# GS_01_Core.net
KiCad netlist of a schematic drawn in Altium Designer
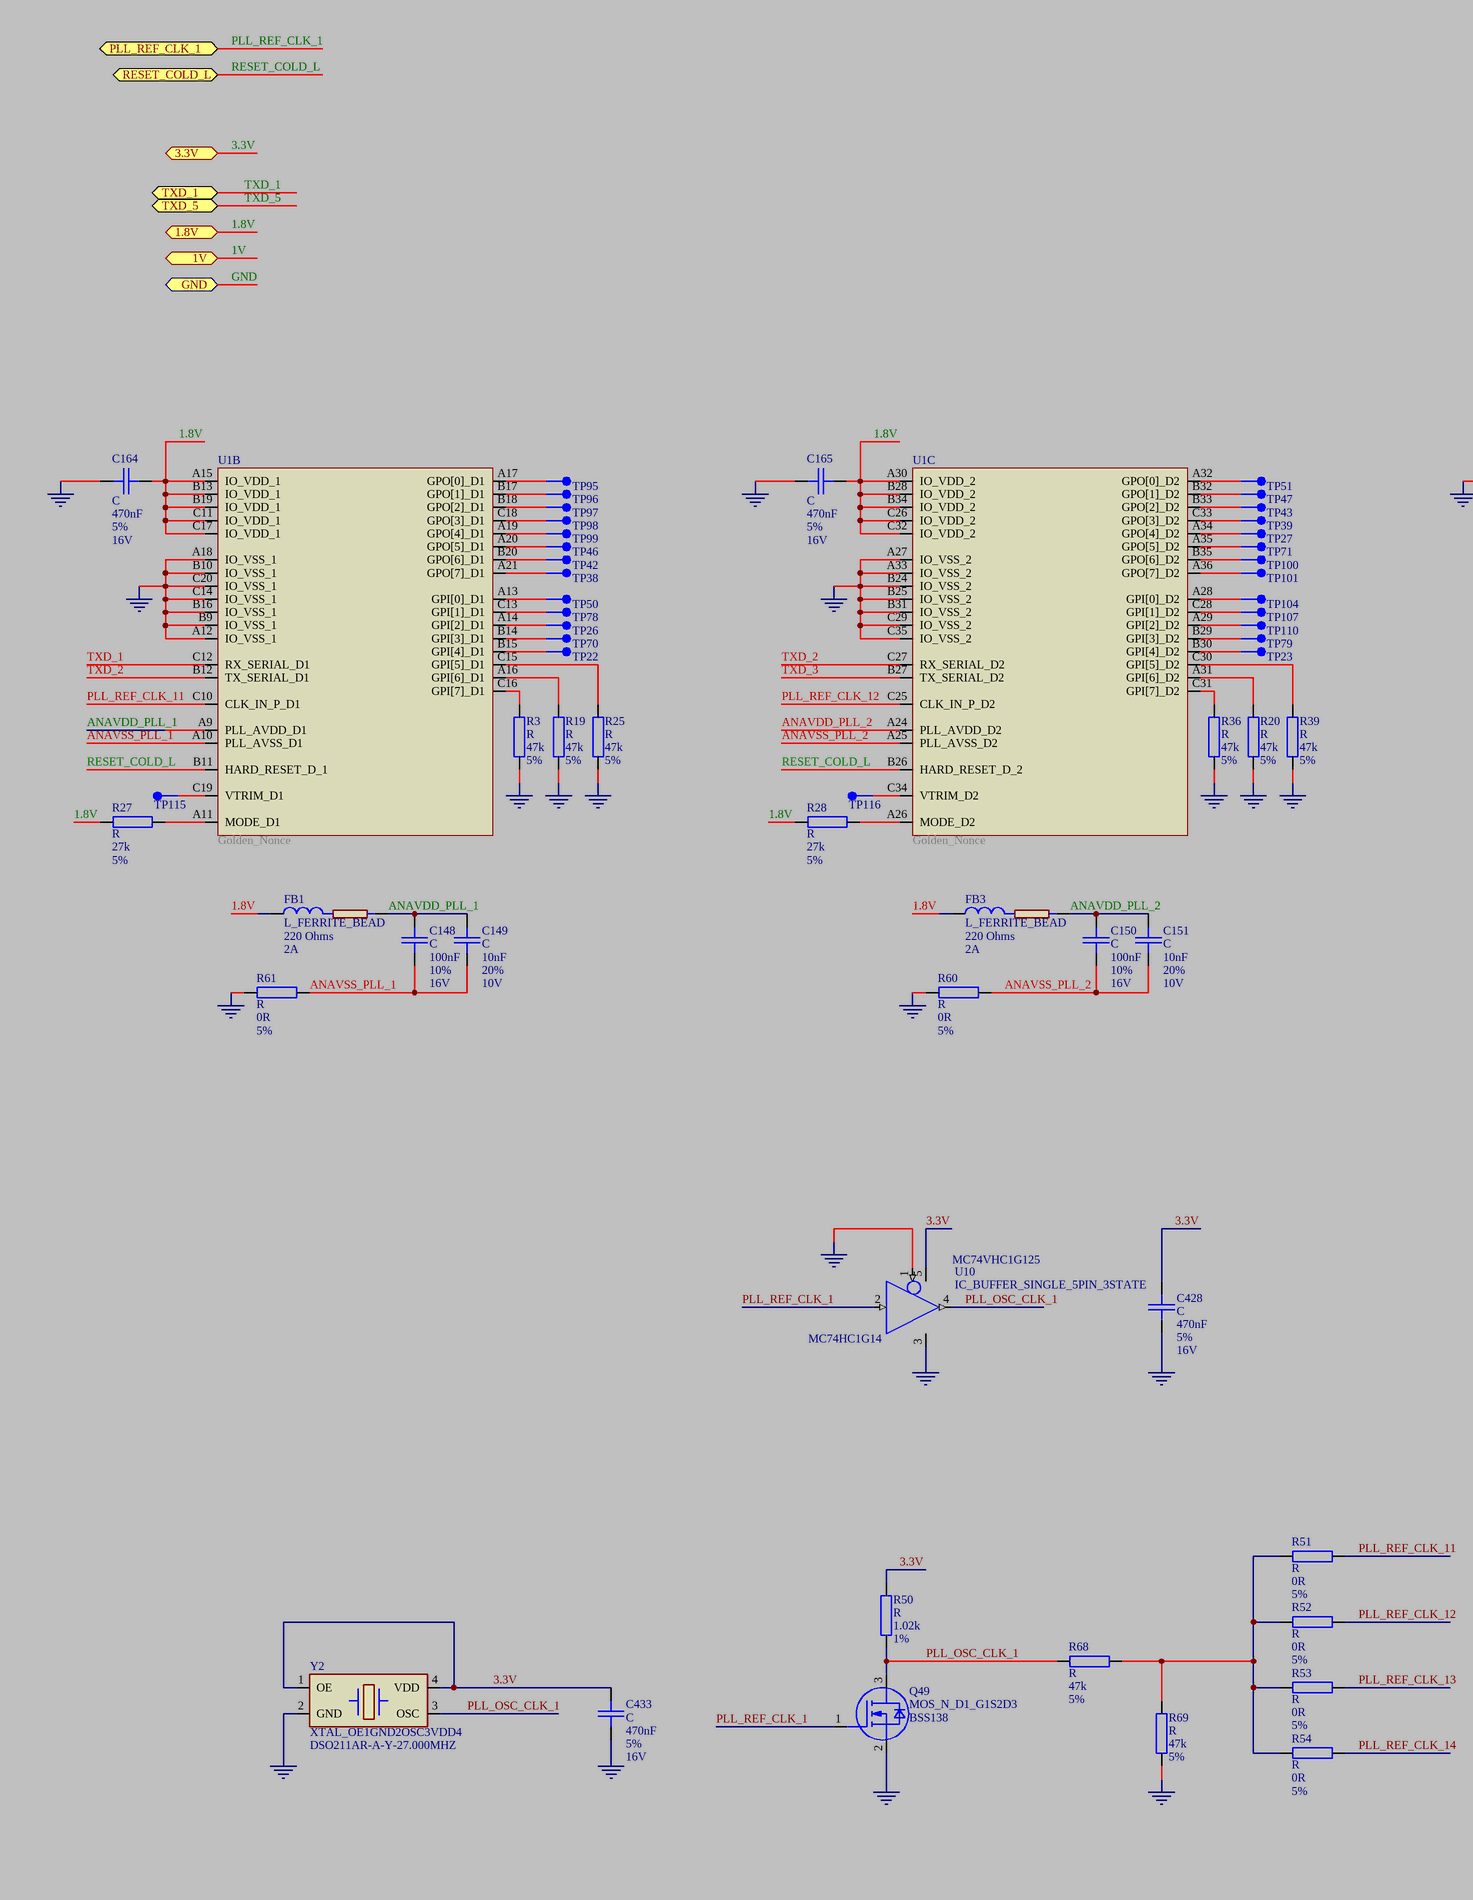
[diagram p0: GS_01_Core.SchDoc, left]
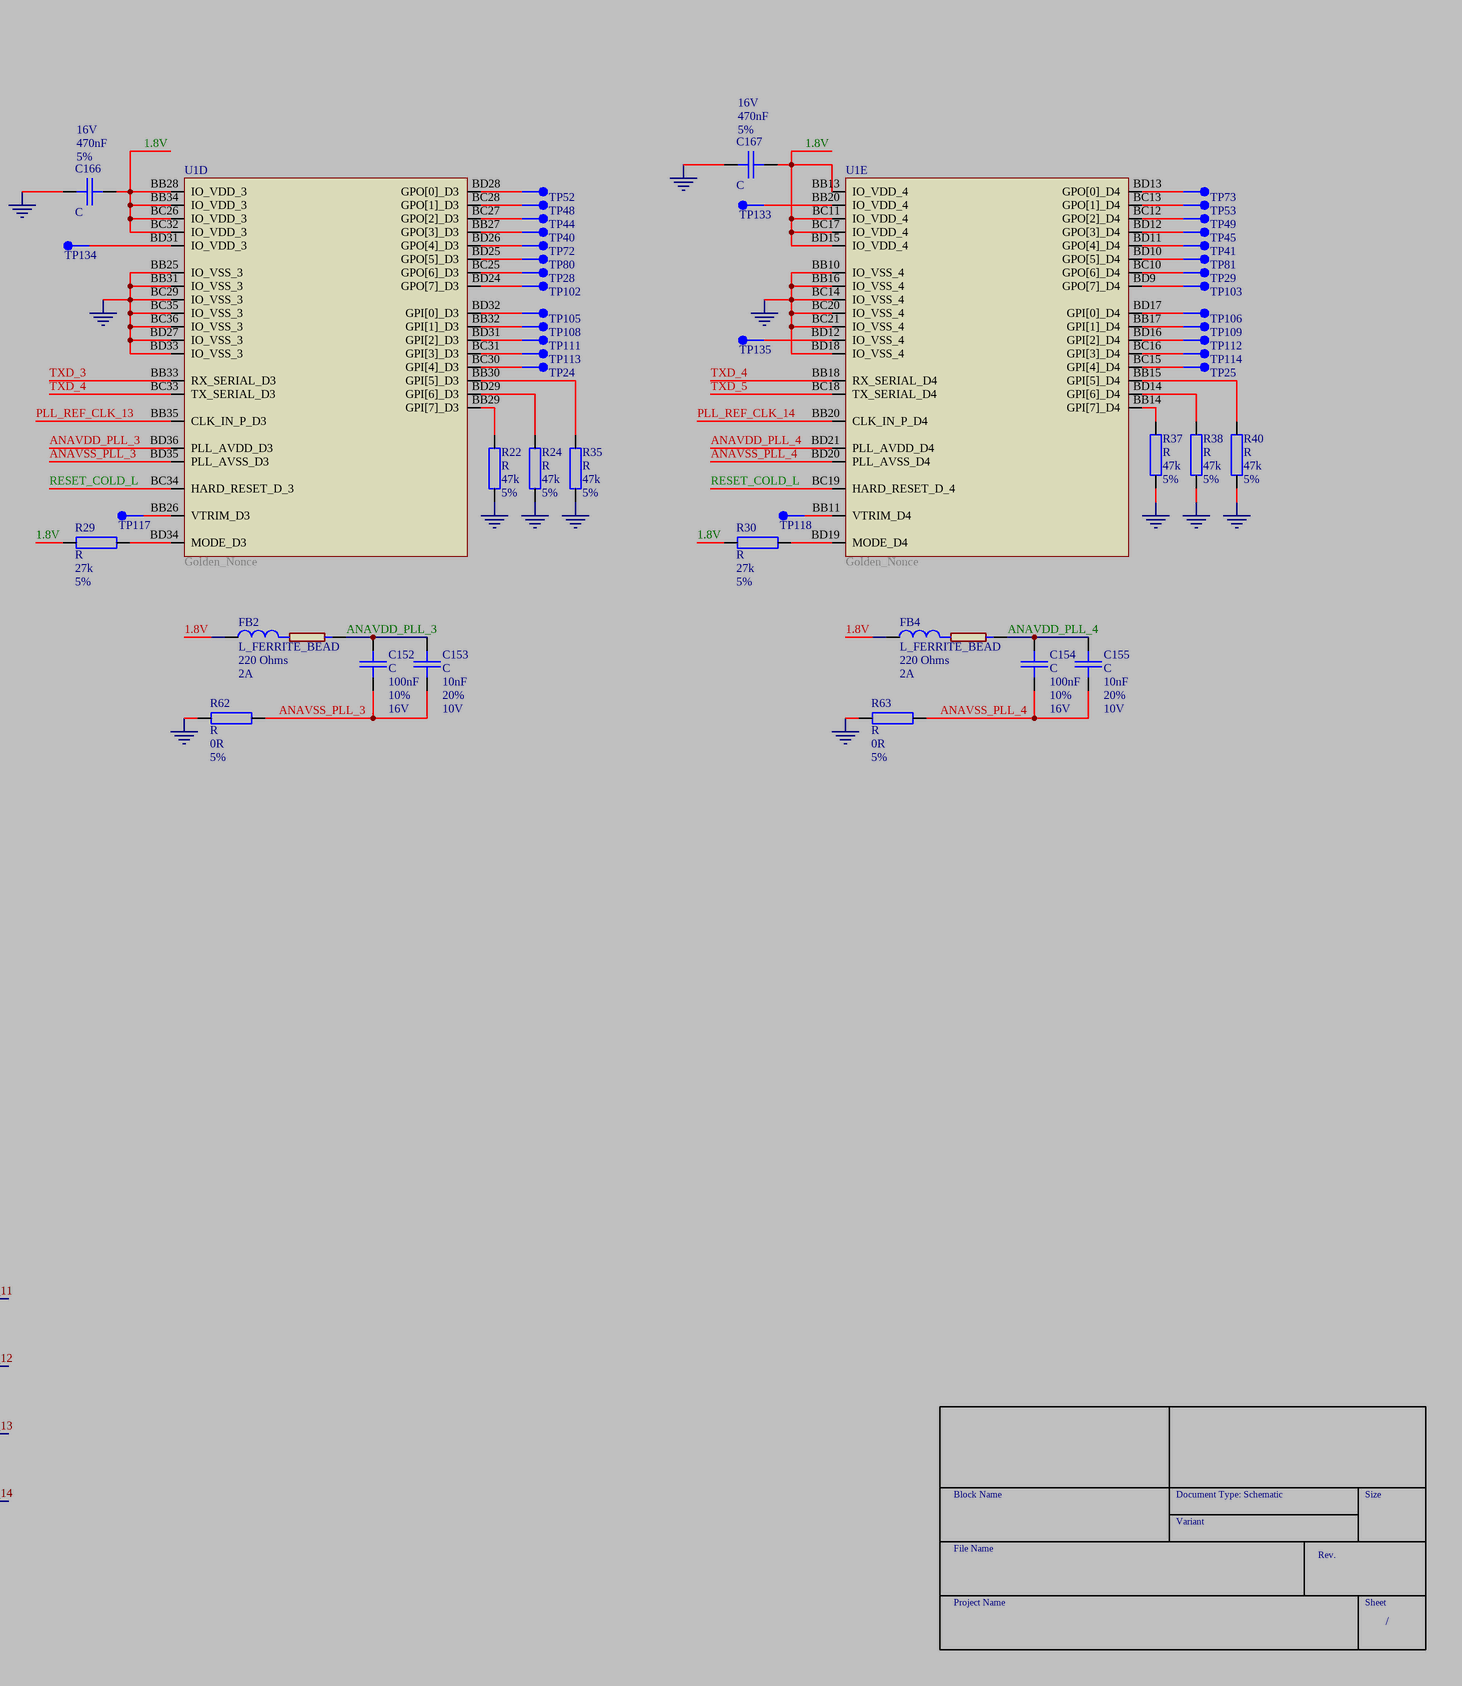
[diagram p1: GS_01_Core.SchDoc, right]

(export (version "E")
  (design (tool "Eeschema 10.0.6"))
  (components
    (comp (ref "C148")
      (value "C")
      (footprint "SMD_0603_CAPC1608X95N")
      (fields
        (field (name "DB_PART_NUMBER") "CAP000047357")
        (field (name "DB_VALUE") "100nF")
        (field (name "DB_TOLERANCE") "10%")
        (field (name "DB_VOLTAGE") "16V")
        (field (name "DB_MANUFACTURER_PART") "YAGEO      223878615649")
        (field (name "DB_APPROVED_BY") "VSN")
      )
      (libsource (lib "Database_Libs1") (part "C"))
    )
    (comp (ref "C149")
      (value "C")
      (footprint "SMD_0603_CAPC1608X95N")
      (fields
        (field (name "DB_PART_NUMBER") "CAP000038821")
        (field (name "DB_VALUE") "10nF")
        (field (name "DB_TOLERANCE") "20%")
        (field (name "DB_VOLTAGE") "10V")
        (field (name "DB_MANUFACTURER_PART") "KEMET    C0603C103M8GAC")
      )
      (libsource (lib "Database_Libs1") (part "C"))
    )
    (comp (ref "C150")
      (value "C")
      (footprint "SMD_0603_CAPC1608X95N")
      (fields
        (field (name "DB_PART_NUMBER") "CAP000047357")
        (field (name "DB_VALUE") "100nF")
        (field (name "DB_TOLERANCE") "10%")
        (field (name "DB_VOLTAGE") "16V")
        (field (name "DB_MANUFACTURER_PART") "YAGEO      223878615649")
        (field (name "DB_APPROVED_BY") "VSN")
      )
      (libsource (lib "Database_Libs1") (part "C"))
    )
    (comp (ref "C151")
      (value "C")
      (footprint "SMD_0603_CAPC1608X95N")
      (fields
        (field (name "DB_PART_NUMBER") "CAP000038821")
        (field (name "DB_VALUE") "10nF")
        (field (name "DB_TOLERANCE") "20%")
        (field (name "DB_VOLTAGE") "10V")
        (field (name "DB_MANUFACTURER_PART") "KEMET    C0603C103M8GAC")
      )
      (libsource (lib "Database_Libs1") (part "C"))
    )
    (comp (ref "C152")
      (value "C")
      (footprint "SMD_0603_CAPC1608X95N")
      (fields
        (field (name "DB_PART_NUMBER") "CAP000047357")
        (field (name "DB_VALUE") "100nF")
        (field (name "DB_TOLERANCE") "10%")
        (field (name "DB_VOLTAGE") "16V")
        (field (name "DB_MANUFACTURER_PART") "YAGEO      223878615649")
        (field (name "DB_APPROVED_BY") "VSN")
      )
      (libsource (lib "Database_Libs1") (part "C"))
    )
    (comp (ref "C153")
      (value "C")
      (footprint "SMD_0603_CAPC1608X95N")
      (fields
        (field (name "DB_PART_NUMBER") "CAP000038821")
        (field (name "DB_VALUE") "10nF")
        (field (name "DB_TOLERANCE") "20%")
        (field (name "DB_VOLTAGE") "10V")
        (field (name "DB_MANUFACTURER_PART") "KEMET    C0603C103M8GAC")
      )
      (libsource (lib "Database_Libs1") (part "C"))
    )
    (comp (ref "C154")
      (value "C")
      (footprint "SMD_0603_CAPC1608X95N")
      (fields
        (field (name "DB_PART_NUMBER") "CAP000047357")
        (field (name "DB_VALUE") "100nF")
        (field (name "DB_TOLERANCE") "10%")
        (field (name "DB_VOLTAGE") "16V")
        (field (name "DB_MANUFACTURER_PART") "YAGEO      223878615649")
        (field (name "DB_APPROVED_BY") "VSN")
      )
      (libsource (lib "Database_Libs1") (part "C"))
    )
    (comp (ref "C155")
      (value "C")
      (footprint "SMD_0603_CAPC1608X95N")
      (fields
        (field (name "DB_PART_NUMBER") "CAP000038821")
        (field (name "DB_VALUE") "10nF")
        (field (name "DB_TOLERANCE") "20%")
        (field (name "DB_VOLTAGE") "10V")
        (field (name "DB_MANUFACTURER_PART") "KEMET    C0603C103M8GAC")
      )
      (libsource (lib "Database_Libs1") (part "C"))
    )
    (comp (ref "C164")
      (value "C")
      (footprint "SMD_0603_CAPC1608X95N")
      (fields
        (field (name "DB_PART_NUMBER") "CAP000028169")
        (field (name "DB_VALUE") "470nF")
        (field (name "DB_TOLERANCE") "5%")
        (field (name "DB_VOLTAGE") "16V")
        (field (name "DB_MANUFACTURER_PART") "KEMET    C0603C474J4RAC")
      )
      (libsource (lib "Database_Libs1") (part "C"))
    )
    (comp (ref "C165")
      (value "C")
      (footprint "SMD_0603_CAPC1608X95N")
      (fields
        (field (name "DB_PART_NUMBER") "CAP000028169")
        (field (name "DB_VALUE") "470nF")
        (field (name "DB_TOLERANCE") "5%")
        (field (name "DB_VOLTAGE") "16V")
        (field (name "DB_MANUFACTURER_PART") "KEMET    C0603C474J4RAC")
      )
      (libsource (lib "Database_Libs1") (part "C"))
    )
    (comp (ref "C166")
      (value "C")
      (footprint "SMD_0603_CAPC1608X95N")
      (fields
        (field (name "DB_PART_NUMBER") "CAP000028169")
        (field (name "DB_VALUE") "470nF")
        (field (name "DB_TOLERANCE") "5%")
        (field (name "DB_VOLTAGE") "16V")
        (field (name "DB_MANUFACTURER_PART") "KEMET    C0603C474J4RAC")
      )
      (libsource (lib "Database_Libs1") (part "C"))
    )
    (comp (ref "C167")
      (value "C")
      (footprint "SMD_0603_CAPC1608X95N")
      (fields
        (field (name "DB_PART_NUMBER") "CAP000028169")
        (field (name "DB_VALUE") "470nF")
        (field (name "DB_TOLERANCE") "5%")
        (field (name "DB_VOLTAGE") "16V")
        (field (name "DB_MANUFACTURER_PART") "KEMET    C0603C474J4RAC")
      )
      (libsource (lib "Database_Libs1") (part "C"))
    )
    (comp (ref "C428")
      (value "C")
      (footprint "SMD_0603_CAPC1608X95N")
      (fields
        (field (name "DB_PART_NUMBER") "CAP000028169")
        (field (name "DB_VALUE") "470nF")
        (field (name "DB_TOLERANCE") "5%")
        (field (name "DB_VOLTAGE") "16V")
        (field (name "DB_MANUFACTURER_PART") "KEMET    C0603C474J4RAC")
      )
      (libsource (lib "Database_Libs1") (part "C"))
    )
    (comp (ref "C433")
      (value "C")
      (footprint "SMD_0603_CAPC1608X95N")
      (fields
        (field (name "DB_PART_NUMBER") "CAP000028169")
        (field (name "DB_VALUE") "470nF")
        (field (name "DB_TOLERANCE") "5%")
        (field (name "DB_VOLTAGE") "16V")
        (field (name "DB_MANUFACTURER_PART") "KEMET    C0603C474J4RAC")
      )
      (libsource (lib "Database_Libs1") (part "C"))
    )
    (comp (ref "FB1")
      (value "L_FERRITE_BEAD")
      (footprint "SMD_0805_INDC2012X105N")
      (fields
        (field (name "DB_PART_NUMBER") "IND000000029")
        (field (name "DB_VALUE") "220 Ohms")
        (field (name "DB_CURRENT") "2A")
        (field (name "DB_MANUFACTURER_PART") "MURATA       BLM21PG221SN1D")
        (field (name "DB_APPROVED_BY") "VSN")
      )
      (libsource (lib "Database_Libs1") (part "L_FERRITE_BEAD"))
    )
    (comp (ref "FB2")
      (value "L_FERRITE_BEAD")
      (footprint "SMD_0805_INDC2012X105N")
      (fields
        (field (name "DB_PART_NUMBER") "IND000000029")
        (field (name "DB_VALUE") "220 Ohms")
        (field (name "DB_CURRENT") "2A")
        (field (name "DB_MANUFACTURER_PART") "MURATA       BLM21PG221SN1D")
        (field (name "DB_APPROVED_BY") "VSN")
      )
      (libsource (lib "Database_Libs1") (part "L_FERRITE_BEAD"))
    )
    (comp (ref "FB3")
      (value "L_FERRITE_BEAD")
      (footprint "SMD_0805_INDC2012X105N")
      (fields
        (field (name "DB_PART_NUMBER") "IND000000029")
        (field (name "DB_VALUE") "220 Ohms")
        (field (name "DB_CURRENT") "2A")
        (field (name "DB_MANUFACTURER_PART") "MURATA       BLM21PG221SN1D")
        (field (name "DB_APPROVED_BY") "VSN")
      )
      (libsource (lib "Database_Libs1") (part "L_FERRITE_BEAD"))
    )
    (comp (ref "FB4")
      (value "L_FERRITE_BEAD")
      (footprint "SMD_0805_INDC2012X105N")
      (fields
        (field (name "DB_PART_NUMBER") "IND000000029")
        (field (name "DB_VALUE") "220 Ohms")
        (field (name "DB_CURRENT") "2A")
        (field (name "DB_MANUFACTURER_PART") "MURATA       BLM21PG221SN1D")
        (field (name "DB_APPROVED_BY") "VSN")
      )
      (libsource (lib "Database_Libs1") (part "L_FERRITE_BEAD"))
    )
    (comp (ref "Q49")
      (value "MOS_N_D1_G1S2D3")
      (footprint "SMD_SOT23_SOT95P240X112-3N")
      (fields
        (field (name "DB_PART_NUMBER") "TRA000001460")
        (field (name "DB_VALUE") "BSS138")
        (field (name "DB_MANUFACTURER_PART") "FAIRCHILD        BSS138LT1G")
        (field (name "DB_APPROVED_BY") "VSN")
      )
      (libsource (lib "Database_Libs1") (part "MOS_N_D1_G1S2D3"))
    )
    (comp (ref "R3")
      (value "R")
      (footprint "SMD_0603_RESC1608X55N")
      (fields
        (field (name "DB_PART_NUMBER") "RES000006462")
        (field (name "DB_VALUE") "47k")
        (field (name "DB_TOLERANCE") "5%")
        (field (name "DB_MANUFACTURER_PART") "YAGEO    RC0603JR-0747K")
      )
      (libsource (lib "Database_Libs1") (part "R"))
    )
    (comp (ref "R19")
      (value "R")
      (footprint "SMD_0603_RESC1608X55N")
      (fields
        (field (name "DB_PART_NUMBER") "RES000006462")
        (field (name "DB_VALUE") "47k")
        (field (name "DB_TOLERANCE") "5%")
        (field (name "DB_MANUFACTURER_PART") "YAGEO    RC0603JR-0747K")
      )
      (libsource (lib "Database_Libs1") (part "R"))
    )
    (comp (ref "R20")
      (value "R")
      (footprint "SMD_0603_RESC1608X55N")
      (fields
        (field (name "DB_PART_NUMBER") "RES000006462")
        (field (name "DB_VALUE") "47k")
        (field (name "DB_TOLERANCE") "5%")
        (field (name "DB_MANUFACTURER_PART") "YAGEO    RC0603JR-0747K")
      )
      (libsource (lib "Database_Libs1") (part "R"))
    )
    (comp (ref "R22")
      (value "R")
      (footprint "SMD_0603_RESC1608X55N")
      (fields
        (field (name "DB_PART_NUMBER") "RES000006462")
        (field (name "DB_VALUE") "47k")
        (field (name "DB_TOLERANCE") "5%")
        (field (name "DB_MANUFACTURER_PART") "YAGEO    RC0603JR-0747K")
      )
      (libsource (lib "Database_Libs1") (part "R"))
    )
    (comp (ref "R24")
      (value "R")
      (footprint "SMD_0603_RESC1608X55N")
      (fields
        (field (name "DB_PART_NUMBER") "RES000006462")
        (field (name "DB_VALUE") "47k")
        (field (name "DB_TOLERANCE") "5%")
        (field (name "DB_MANUFACTURER_PART") "YAGEO    RC0603JR-0747K")
      )
      (libsource (lib "Database_Libs1") (part "R"))
    )
    (comp (ref "R25")
      (value "R")
      (footprint "SMD_0603_RESC1608X55N")
      (fields
        (field (name "DB_PART_NUMBER") "RES000006462")
        (field (name "DB_VALUE") "47k")
        (field (name "DB_TOLERANCE") "5%")
        (field (name "DB_MANUFACTURER_PART") "YAGEO    RC0603JR-0747K")
      )
      (libsource (lib "Database_Libs1") (part "R"))
    )
    (comp (ref "R27")
      (value "R")
      (footprint "SMD_0603_RESC1608X55N")
      (fields
        (field (name "DB_PART_NUMBER") "RES000006456")
        (field (name "DB_VALUE") "27k")
        (field (name "DB_TOLERANCE") "5%")
        (field (name "DB_MANUFACTURER_PART") "YAGEO    RC0603JR-0727K")
      )
      (libsource (lib "Database_Libs1") (part "R"))
    )
    (comp (ref "R28")
      (value "R")
      (footprint "SMD_0603_RESC1608X55N")
      (fields
        (field (name "DB_PART_NUMBER") "RES000006456")
        (field (name "DB_VALUE") "27k")
        (field (name "DB_TOLERANCE") "5%")
        (field (name "DB_MANUFACTURER_PART") "YAGEO    RC0603JR-0727K")
      )
      (libsource (lib "Database_Libs1") (part "R"))
    )
    (comp (ref "R29")
      (value "R")
      (footprint "SMD_0603_RESC1608X55N")
      (fields
        (field (name "DB_PART_NUMBER") "RES000006456")
        (field (name "DB_VALUE") "27k")
        (field (name "DB_TOLERANCE") "5%")
        (field (name "DB_MANUFACTURER_PART") "YAGEO    RC0603JR-0727K")
      )
      (libsource (lib "Database_Libs1") (part "R"))
    )
    (comp (ref "R30")
      (value "R")
      (footprint "SMD_0603_RESC1608X55N")
      (fields
        (field (name "DB_PART_NUMBER") "RES000006456")
        (field (name "DB_VALUE") "27k")
        (field (name "DB_TOLERANCE") "5%")
        (field (name "DB_MANUFACTURER_PART") "YAGEO    RC0603JR-0727K")
      )
      (libsource (lib "Database_Libs1") (part "R"))
    )
    (comp (ref "R35")
      (value "R")
      (footprint "SMD_0603_RESC1608X55N")
      (fields
        (field (name "DB_PART_NUMBER") "RES000006462")
        (field (name "DB_VALUE") "47k")
        (field (name "DB_TOLERANCE") "5%")
        (field (name "DB_MANUFACTURER_PART") "YAGEO    RC0603JR-0747K")
      )
      (libsource (lib "Database_Libs1") (part "R"))
    )
    (comp (ref "R36")
      (value "R")
      (footprint "SMD_0603_RESC1608X55N")
      (fields
        (field (name "DB_PART_NUMBER") "RES000006462")
        (field (name "DB_VALUE") "47k")
        (field (name "DB_TOLERANCE") "5%")
        (field (name "DB_MANUFACTURER_PART") "YAGEO    RC0603JR-0747K")
      )
      (libsource (lib "Database_Libs1") (part "R"))
    )
    (comp (ref "R37")
      (value "R")
      (footprint "SMD_0603_RESC1608X55N")
      (fields
        (field (name "DB_PART_NUMBER") "RES000006462")
        (field (name "DB_VALUE") "47k")
        (field (name "DB_TOLERANCE") "5%")
        (field (name "DB_MANUFACTURER_PART") "YAGEO    RC0603JR-0747K")
      )
      (libsource (lib "Database_Libs1") (part "R"))
    )
    (comp (ref "R38")
      (value "R")
      (footprint "SMD_0603_RESC1608X55N")
      (fields
        (field (name "DB_PART_NUMBER") "RES000006462")
        (field (name "DB_VALUE") "47k")
        (field (name "DB_TOLERANCE") "5%")
        (field (name "DB_MANUFACTURER_PART") "YAGEO    RC0603JR-0747K")
      )
      (libsource (lib "Database_Libs1") (part "R"))
    )
    (comp (ref "R39")
      (value "R")
      (footprint "SMD_0603_RESC1608X55N")
      (fields
        (field (name "DB_PART_NUMBER") "RES000006462")
        (field (name "DB_VALUE") "47k")
        (field (name "DB_TOLERANCE") "5%")
        (field (name "DB_MANUFACTURER_PART") "YAGEO    RC0603JR-0747K")
      )
      (libsource (lib "Database_Libs1") (part "R"))
    )
    (comp (ref "R40")
      (value "R")
      (footprint "SMD_0603_RESC1608X55N")
      (fields
        (field (name "DB_PART_NUMBER") "RES000006462")
        (field (name "DB_VALUE") "47k")
        (field (name "DB_TOLERANCE") "5%")
        (field (name "DB_MANUFACTURER_PART") "YAGEO    RC0603JR-0747K")
      )
      (libsource (lib "Database_Libs1") (part "R"))
    )
    (comp (ref "R50")
      (value "R")
      (footprint "SMD_0603_RESC1608X55N")
      (fields
        (field (name "DB_PART_NUMBER") "RES000001446")
        (field (name "DB_VALUE") "1.02k")
        (field (name "DB_TOLERANCE") "1%")
        (field (name "DB_MANUFACTURER_PART") "YAGEO    RC0603FR-071K02")
      )
      (libsource (lib "Database_Libs1") (part "R"))
    )
    (comp (ref "R51")
      (value "R")
      (footprint "SMD_0603_RESC1608X55N")
      (fields
        (field (name "DB_PART_NUMBER") "RES000006349")
        (field (name "DB_VALUE") "0R")
        (field (name "DB_TOLERANCE") "5%")
        (field (name "DB_MANUFACTURER_PART") "YAGEO    RC0603JR-070R")
      )
      (libsource (lib "Database_Libs1") (part "R"))
    )
    (comp (ref "R52")
      (value "R")
      (footprint "SMD_0603_RESC1608X55N")
      (fields
        (field (name "DB_PART_NUMBER") "RES000006349")
        (field (name "DB_VALUE") "0R")
        (field (name "DB_TOLERANCE") "5%")
        (field (name "DB_MANUFACTURER_PART") "YAGEO    RC0603JR-070R")
      )
      (libsource (lib "Database_Libs1") (part "R"))
    )
    (comp (ref "R53")
      (value "R")
      (footprint "SMD_0603_RESC1608X55N")
      (fields
        (field (name "DB_PART_NUMBER") "RES000006349")
        (field (name "DB_VALUE") "0R")
        (field (name "DB_TOLERANCE") "5%")
        (field (name "DB_MANUFACTURER_PART") "YAGEO    RC0603JR-070R")
      )
      (libsource (lib "Database_Libs1") (part "R"))
    )
    (comp (ref "R54")
      (value "R")
      (footprint "SMD_0603_RESC1608X55N")
      (fields
        (field (name "DB_PART_NUMBER") "RES000006349")
        (field (name "DB_VALUE") "0R")
        (field (name "DB_TOLERANCE") "5%")
        (field (name "DB_MANUFACTURER_PART") "YAGEO    RC0603JR-070R")
      )
      (libsource (lib "Database_Libs1") (part "R"))
    )
    (comp (ref "R60")
      (value "R")
      (footprint "SMD_0402_RESC1005X37N")
      (fields
        (field (name "DB_PART_NUMBER") "RES000006002")
        (field (name "DB_VALUE") "0R")
        (field (name "DB_TOLERANCE") "5%")
        (field (name "DB_MANUFACTURER_PART") "YAGEO    RC0402JR-070R")
      )
      (libsource (lib "Database_Libs1") (part "R"))
    )
    (comp (ref "R61")
      (value "R")
      (footprint "SMD_0402_RESC1005X37N")
      (fields
        (field (name "DB_PART_NUMBER") "RES000006002")
        (field (name "DB_VALUE") "0R")
        (field (name "DB_TOLERANCE") "5%")
        (field (name "DB_MANUFACTURER_PART") "YAGEO    RC0402JR-070R")
      )
      (libsource (lib "Database_Libs1") (part "R"))
    )
    (comp (ref "R62")
      (value "R")
      (footprint "SMD_0402_RESC1005X37N")
      (fields
        (field (name "DB_PART_NUMBER") "RES000006002")
        (field (name "DB_VALUE") "0R")
        (field (name "DB_TOLERANCE") "5%")
        (field (name "DB_MANUFACTURER_PART") "YAGEO    RC0402JR-070R")
      )
      (libsource (lib "Database_Libs1") (part "R"))
    )
    (comp (ref "R63")
      (value "R")
      (footprint "SMD_0402_RESC1005X37N")
      (fields
        (field (name "DB_PART_NUMBER") "RES000006002")
        (field (name "DB_VALUE") "0R")
        (field (name "DB_TOLERANCE") "5%")
        (field (name "DB_MANUFACTURER_PART") "YAGEO    RC0402JR-070R")
      )
      (libsource (lib "Database_Libs1") (part "R"))
    )
    (comp (ref "R68")
      (value "R")
      (footprint "SMD_0603_RESC1608X55N")
      (fields
        (field (name "DB_PART_NUMBER") "RES000006462")
        (field (name "DB_VALUE") "47k")
        (field (name "DB_TOLERANCE") "5%")
        (field (name "DB_MANUFACTURER_PART") "YAGEO    RC0603JR-0747K")
      )
      (libsource (lib "Database_Libs1") (part "R"))
    )
    (comp (ref "R69")
      (value "R")
      (footprint "SMD_0603_RESC1608X55N")
      (fields
        (field (name "DB_PART_NUMBER") "RES000006462")
        (field (name "DB_VALUE") "47k")
        (field (name "DB_TOLERANCE") "5%")
        (field (name "DB_MANUFACTURER_PART") "YAGEO    RC0603JR-0747K")
      )
      (libsource (lib "Database_Libs1") (part "R"))
    )
    (comp (ref "TP22")
      (value "TEST_POINT_1")
      (footprint "SMD_TP_100-254")
      (fields (field (name "DB_PART_NUMBER") "TPO000000001"))
      (libsource (lib "Database_Libs1") (part "TEST_POINT_1"))
    )
    (comp (ref "TP23")
      (value "TEST_POINT_1")
      (footprint "SMD_TP_100-254")
      (fields (field (name "DB_PART_NUMBER") "TPO000000001"))
      (libsource (lib "Database_Libs1") (part "TEST_POINT_1"))
    )
    (comp (ref "TP24")
      (value "TEST_POINT_1")
      (footprint "SMD_TP_100-254")
      (fields (field (name "DB_PART_NUMBER") "TPO000000001"))
      (libsource (lib "Database_Libs1") (part "TEST_POINT_1"))
    )
    (comp (ref "TP25")
      (value "TEST_POINT_1")
      (footprint "SMD_TP_100-254")
      (fields (field (name "DB_PART_NUMBER") "TPO000000001"))
      (libsource (lib "Database_Libs1") (part "TEST_POINT_1"))
    )
    (comp (ref "TP26")
      (value "TEST_POINT_1")
      (footprint "SMD_TP_100-254")
      (fields (field (name "DB_PART_NUMBER") "TPO000000001"))
      (libsource (lib "Database_Libs1") (part "TEST_POINT_1"))
    )
    (comp (ref "TP27")
      (value "TEST_POINT_1")
      (footprint "SMD_TP_100-254")
      (fields (field (name "DB_PART_NUMBER") "TPO000000001"))
      (libsource (lib "Database_Libs1") (part "TEST_POINT_1"))
    )
    (comp (ref "TP28")
      (value "TEST_POINT_1")
      (footprint "SMD_TP_100-254")
      (fields (field (name "DB_PART_NUMBER") "TPO000000001"))
      (libsource (lib "Database_Libs1") (part "TEST_POINT_1"))
    )
    (comp (ref "TP29")
      (value "TEST_POINT_1")
      (footprint "SMD_TP_100-254")
      (fields (field (name "DB_PART_NUMBER") "TPO000000001"))
      (libsource (lib "Database_Libs1") (part "TEST_POINT_1"))
    )
    (comp (ref "TP38")
      (value "TEST_POINT_1")
      (footprint "SMD_TP_100-254")
      (fields (field (name "DB_PART_NUMBER") "TPO000000001"))
      (libsource (lib "Database_Libs1") (part "TEST_POINT_1"))
    )
    (comp (ref "TP39")
      (value "TEST_POINT_1")
      (footprint "SMD_TP_100-254")
      (fields (field (name "DB_PART_NUMBER") "TPO000000001"))
      (libsource (lib "Database_Libs1") (part "TEST_POINT_1"))
    )
    (comp (ref "TP40")
      (value "TEST_POINT_1")
      (footprint "SMD_TP_100-254")
      (fields (field (name "DB_PART_NUMBER") "TPO000000001"))
      (libsource (lib "Database_Libs1") (part "TEST_POINT_1"))
    )
    (comp (ref "TP41")
      (value "TEST_POINT_1")
      (footprint "SMD_TP_100-254")
      (fields (field (name "DB_PART_NUMBER") "TPO000000001"))
      (libsource (lib "Database_Libs1") (part "TEST_POINT_1"))
    )
    (comp (ref "TP42")
      (value "TEST_POINT_1")
      (footprint "SMD_TP_100-254")
      (fields (field (name "DB_PART_NUMBER") "TPO000000001"))
      (libsource (lib "Database_Libs1") (part "TEST_POINT_1"))
    )
    (comp (ref "TP43")
      (value "TEST_POINT_1")
      (footprint "SMD_TP_100-254")
      (fields (field (name "DB_PART_NUMBER") "TPO000000001"))
      (libsource (lib "Database_Libs1") (part "TEST_POINT_1"))
    )
    (comp (ref "TP44")
      (value "TEST_POINT_1")
      (footprint "SMD_TP_100-254")
      (fields (field (name "DB_PART_NUMBER") "TPO000000001"))
      (libsource (lib "Database_Libs1") (part "TEST_POINT_1"))
    )
    (comp (ref "TP45")
      (value "TEST_POINT_1")
      (footprint "SMD_TP_100-254")
      (fields (field (name "DB_PART_NUMBER") "TPO000000001"))
      (libsource (lib "Database_Libs1") (part "TEST_POINT_1"))
    )
    (comp (ref "TP46")
      (value "TEST_POINT_1")
      (footprint "SMD_TP_100-254")
      (fields (field (name "DB_PART_NUMBER") "TPO000000001"))
      (libsource (lib "Database_Libs1") (part "TEST_POINT_1"))
    )
    (comp (ref "TP47")
      (value "TEST_POINT_1")
      (footprint "SMD_TP_100-254")
      (fields (field (name "DB_PART_NUMBER") "TPO000000001"))
      (libsource (lib "Database_Libs1") (part "TEST_POINT_1"))
    )
    (comp (ref "TP48")
      (value "TEST_POINT_1")
      (footprint "SMD_TP_100-254")
      (fields (field (name "DB_PART_NUMBER") "TPO000000001"))
      (libsource (lib "Database_Libs1") (part "TEST_POINT_1"))
    )
    (comp (ref "TP49")
      (value "TEST_POINT_1")
      (footprint "SMD_TP_100-254")
      (fields (field (name "DB_PART_NUMBER") "TPO000000001"))
      (libsource (lib "Database_Libs1") (part "TEST_POINT_1"))
    )
    (comp (ref "TP50")
      (value "TEST_POINT_1")
      (footprint "SMD_TP_100-254")
      (fields (field (name "DB_PART_NUMBER") "TPO000000001"))
      (libsource (lib "Database_Libs1") (part "TEST_POINT_1"))
    )
    (comp (ref "TP51")
      (value "TEST_POINT_1")
      (footprint "SMD_TP_100-254")
      (fields (field (name "DB_PART_NUMBER") "TPO000000001"))
      (libsource (lib "Database_Libs1") (part "TEST_POINT_1"))
    )
    (comp (ref "TP52")
      (value "TEST_POINT_1")
      (footprint "SMD_TP_100-254")
      (fields (field (name "DB_PART_NUMBER") "TPO000000001"))
      (libsource (lib "Database_Libs1") (part "TEST_POINT_1"))
    )
    (comp (ref "TP53")
      (value "TEST_POINT_1")
      (footprint "SMD_TP_100-254")
      (fields (field (name "DB_PART_NUMBER") "TPO000000001"))
      (libsource (lib "Database_Libs1") (part "TEST_POINT_1"))
    )
    (comp (ref "TP70")
      (value "TEST_POINT_1")
      (footprint "SMD_TP_100-254")
      (fields (field (name "DB_PART_NUMBER") "TPO000000001"))
      (libsource (lib "Database_Libs1") (part "TEST_POINT_1"))
    )
    (comp (ref "TP71")
      (value "TEST_POINT_1")
      (footprint "SMD_TP_100-254")
      (fields (field (name "DB_PART_NUMBER") "TPO000000001"))
      (libsource (lib "Database_Libs1") (part "TEST_POINT_1"))
    )
    (comp (ref "TP72")
      (value "TEST_POINT_1")
      (footprint "SMD_TP_100-254")
      (fields (field (name "DB_PART_NUMBER") "TPO000000001"))
      (libsource (lib "Database_Libs1") (part "TEST_POINT_1"))
    )
    (comp (ref "TP73")
      (value "TEST_POINT_1")
      (footprint "SMD_TP_100-254")
      (fields (field (name "DB_PART_NUMBER") "TPO000000001"))
      (libsource (lib "Database_Libs1") (part "TEST_POINT_1"))
    )
    (comp (ref "TP78")
      (value "TEST_POINT_1")
      (footprint "SMD_TP_100-254")
      (fields (field (name "DB_PART_NUMBER") "TPO000000001"))
      (libsource (lib "Database_Libs1") (part "TEST_POINT_1"))
    )
    (comp (ref "TP79")
      (value "TEST_POINT_1")
      (footprint "SMD_TP_100-254")
      (fields (field (name "DB_PART_NUMBER") "TPO000000001"))
      (libsource (lib "Database_Libs1") (part "TEST_POINT_1"))
    )
    (comp (ref "TP80")
      (value "TEST_POINT_1")
      (footprint "SMD_TP_100-254")
      (fields (field (name "DB_PART_NUMBER") "TPO000000001"))
      (libsource (lib "Database_Libs1") (part "TEST_POINT_1"))
    )
    (comp (ref "TP81")
      (value "TEST_POINT_1")
      (footprint "SMD_TP_100-254")
      (fields (field (name "DB_PART_NUMBER") "TPO000000001"))
      (libsource (lib "Database_Libs1") (part "TEST_POINT_1"))
    )
    (comp (ref "TP95")
      (value "TEST_POINT_1")
      (footprint "SMD_TP_100-254")
      (fields (field (name "DB_PART_NUMBER") "TPO000000001"))
      (libsource (lib "Database_Libs1") (part "TEST_POINT_1"))
    )
    (comp (ref "TP96")
      (value "TEST_POINT_1")
      (footprint "SMD_TP_100-254")
      (fields (field (name "DB_PART_NUMBER") "TPO000000001"))
      (libsource (lib "Database_Libs1") (part "TEST_POINT_1"))
    )
    (comp (ref "TP97")
      (value "TEST_POINT_1")
      (footprint "SMD_TP_100-254")
      (fields (field (name "DB_PART_NUMBER") "TPO000000001"))
      (libsource (lib "Database_Libs1") (part "TEST_POINT_1"))
    )
    (comp (ref "TP98")
      (value "TEST_POINT_1")
      (footprint "SMD_TP_100-254")
      (fields (field (name "DB_PART_NUMBER") "TPO000000001"))
      (libsource (lib "Database_Libs1") (part "TEST_POINT_1"))
    )
    (comp (ref "TP99")
      (value "TEST_POINT_1")
      (footprint "SMD_TP_100-254")
      (fields (field (name "DB_PART_NUMBER") "TPO000000001"))
      (libsource (lib "Database_Libs1") (part "TEST_POINT_1"))
    )
    (comp (ref "TP100")
      (value "TEST_POINT_1")
      (footprint "SMD_TP_100-254")
      (fields (field (name "DB_PART_NUMBER") "TPO000000001"))
      (libsource (lib "Database_Libs1") (part "TEST_POINT_1"))
    )
    (comp (ref "TP101")
      (value "TEST_POINT_1")
      (footprint "SMD_TP_100-254")
      (fields (field (name "DB_PART_NUMBER") "TPO000000001"))
      (libsource (lib "Database_Libs1") (part "TEST_POINT_1"))
    )
    (comp (ref "TP102")
      (value "TEST_POINT_1")
      (footprint "SMD_TP_100-254")
      (fields (field (name "DB_PART_NUMBER") "TPO000000001"))
      (libsource (lib "Database_Libs1") (part "TEST_POINT_1"))
    )
    (comp (ref "TP103")
      (value "TEST_POINT_1")
      (footprint "SMD_TP_100-254")
      (fields (field (name "DB_PART_NUMBER") "TPO000000001"))
      (libsource (lib "Database_Libs1") (part "TEST_POINT_1"))
    )
    (comp (ref "TP104")
      (value "TEST_POINT_1")
      (footprint "SMD_TP_100-254")
      (fields (field (name "DB_PART_NUMBER") "TPO000000001"))
      (libsource (lib "Database_Libs1") (part "TEST_POINT_1"))
    )
    (comp (ref "TP105")
      (value "TEST_POINT_1")
      (footprint "SMD_TP_100-254")
      (fields (field (name "DB_PART_NUMBER") "TPO000000001"))
      (libsource (lib "Database_Libs1") (part "TEST_POINT_1"))
    )
    (comp (ref "TP106")
      (value "TEST_POINT_1")
      (footprint "SMD_TP_100-254")
      (fields (field (name "DB_PART_NUMBER") "TPO000000001"))
      (libsource (lib "Database_Libs1") (part "TEST_POINT_1"))
    )
    (comp (ref "TP107")
      (value "TEST_POINT_1")
      (footprint "SMD_TP_100-254")
      (fields (field (name "DB_PART_NUMBER") "TPO000000001"))
      (libsource (lib "Database_Libs1") (part "TEST_POINT_1"))
    )
    (comp (ref "TP108")
      (value "TEST_POINT_1")
      (footprint "SMD_TP_100-254")
      (fields (field (name "DB_PART_NUMBER") "TPO000000001"))
      (libsource (lib "Database_Libs1") (part "TEST_POINT_1"))
    )
    (comp (ref "TP109")
      (value "TEST_POINT_1")
      (footprint "SMD_TP_100-254")
      (fields (field (name "DB_PART_NUMBER") "TPO000000001"))
      (libsource (lib "Database_Libs1") (part "TEST_POINT_1"))
    )
    (comp (ref "TP110")
      (value "TEST_POINT_1")
      (footprint "SMD_TP_100-254")
      (fields (field (name "DB_PART_NUMBER") "TPO000000001"))
      (libsource (lib "Database_Libs1") (part "TEST_POINT_1"))
    )
    (comp (ref "TP111")
      (value "TEST_POINT_1")
      (footprint "SMD_TP_100-254")
      (fields (field (name "DB_PART_NUMBER") "TPO000000001"))
      (libsource (lib "Database_Libs1") (part "TEST_POINT_1"))
    )
    (comp (ref "TP112")
      (value "TEST_POINT_1")
      (footprint "SMD_TP_100-254")
      (fields (field (name "DB_PART_NUMBER") "TPO000000001"))
      (libsource (lib "Database_Libs1") (part "TEST_POINT_1"))
    )
    (comp (ref "TP113")
      (value "TEST_POINT_1")
      (footprint "SMD_TP_100-254")
      (fields (field (name "DB_PART_NUMBER") "TPO000000001"))
      (libsource (lib "Database_Libs1") (part "TEST_POINT_1"))
    )
    (comp (ref "TP114")
      (value "TEST_POINT_1")
      (footprint "SMD_TP_100-254")
      (fields (field (name "DB_PART_NUMBER") "TPO000000001"))
      (libsource (lib "Database_Libs1") (part "TEST_POINT_1"))
    )
    (comp (ref "TP115")
      (value "TEST_POINT_1")
      (footprint "SMD_TP_100-254")
      (fields (field (name "DB_PART_NUMBER") "TPO000000001"))
      (libsource (lib "Database_Libs1") (part "TEST_POINT_1"))
    )
    (comp (ref "TP116")
      (value "TEST_POINT_1")
      (footprint "SMD_TP_100-254")
      (fields (field (name "DB_PART_NUMBER") "TPO000000001"))
      (libsource (lib "Database_Libs1") (part "TEST_POINT_1"))
    )
    (comp (ref "TP117")
      (value "TEST_POINT_1")
      (footprint "SMD_TP_100-254")
      (fields (field (name "DB_PART_NUMBER") "TPO000000001"))
      (libsource (lib "Database_Libs1") (part "TEST_POINT_1"))
    )
    (comp (ref "TP118")
      (value "TEST_POINT_1")
      (footprint "SMD_TP_100-254")
      (fields (field (name "DB_PART_NUMBER") "TPO000000001"))
      (libsource (lib "Database_Libs1") (part "TEST_POINT_1"))
    )
    (comp (ref "TP133")
      (value "TEST_POINT_1")
      (footprint "SMD_TP_100-254")
      (fields (field (name "DB_PART_NUMBER") "TPO000000001"))
      (libsource (lib "Database_Libs1") (part "TEST_POINT_1"))
    )
    (comp (ref "TP134")
      (value "TEST_POINT_1")
      (footprint "SMD_TP_100-254")
      (fields (field (name "DB_PART_NUMBER") "TPO000000001"))
      (libsource (lib "Database_Libs1") (part "TEST_POINT_1"))
    )
    (comp (ref "TP135")
      (value "TEST_POINT_1")
      (footprint "SMD_TP_100-254")
      (fields (field (name "DB_PART_NUMBER") "TPO000000001"))
      (libsource (lib "Database_Libs1") (part "TEST_POINT_1"))
    )
    (comp (ref "U1") (value "Golden_Nonce") (libsource (lib "Schlib1") (part "Golden_Nonce")))
    (comp (ref "U10")
      (value "IC_BUFFER_SINGLE_5PIN_3STATE")
      (footprint "SMD_SOT95P280X110-5N")
      (fields
        (field (name "DB_PART_NUMBER") "DIG000000005")
        (field (name "DB_VALUE") "MC74VHC1G125")
        (field (name "DB_MANUFACTURER_PART") "ON Semiconductor       M74VHC1G125DTT1G")
        (field (name "DB_APPROVED_BY") "VSN")
      )
      (libsource (lib "Database_Libs1") (part "IC_BUFFER_SINGLE_5PIN_3STATE"))
    )
    (comp (ref "Y2")
      (value "XTAL_OE1GND2OSC3VDD4")
      (footprint "SMD_OSCCC500X700X100-4N")
      (fields
        (field (name "DB_PART_NUMBER") "OSC000000015")
        (field (name "DB_VALUE") "DSO211AR-A-Y-27.000MHZ")
        (field (name "DB_MANUFACTURER_PART") "KDS DAISHINKU      DSO211AR-A-Y-27.000MHZ")
        (field (name "DB_APPROVED_BY") "VSN")
      )
      (libsource (lib "Database_Libs1") (part "XTAL_OE1GND2OSC3VDD4"))
    )
  )
  (nets
    (net (code "1") (name "/1.8V") (class "Default")
      (node (ref "C164") (pin "2") (pinfunction "2_2") (pintype "passive"))
      (node (ref "C165") (pin "2") (pinfunction "2_2") (pintype "passive"))
      (node (ref "C166") (pin "2") (pinfunction "2_2") (pintype "passive"))
      (node (ref "C167") (pin "2") (pinfunction "2_2") (pintype "passive"))
      (node (ref "FB1") (pin "1") (pinfunction "1_1") (pintype "passive"))
      (node (ref "FB2") (pin "1") (pinfunction "1_1") (pintype "passive"))
      (node (ref "FB3") (pin "1") (pinfunction "1_1") (pintype "passive"))
      (node (ref "FB4") (pin "1") (pinfunction "1_1") (pintype "passive"))
      (node (ref "R27") (pin "1") (pinfunction "1_1") (pintype "passive"))
      (node (ref "R28") (pin "1") (pinfunction "1_1") (pintype "passive"))
      (node (ref "R29") (pin "1") (pinfunction "1_1") (pintype "passive"))
      (node (ref "R30") (pin "1") (pinfunction "1_1") (pintype "passive"))
      (node (ref "U1") (pin "A15") (pinfunction "IO_VDD_1_A15") (pintype "passive"))
      (node (ref "U1") (pin "A30") (pinfunction "IO_VDD_2_A30") (pintype "passive"))
      (node (ref "U1") (pin "B13") (pinfunction "IO_VDD_1_B13") (pintype "passive"))
      (node (ref "U1") (pin "B19") (pinfunction "IO_VDD_1_B19") (pintype "passive"))
      (node (ref "U1") (pin "B28") (pinfunction "IO_VDD_2_B28") (pintype "passive"))
      (node (ref "U1") (pin "B34") (pinfunction "IO_VDD_2_B34") (pintype "passive"))
      (node (ref "U1") (pin "BB13") (pinfunction "IO_VDD_4_BB13") (pintype "passive"))
      (node (ref "U1") (pin "BB28") (pinfunction "IO_VDD_3_BB28") (pintype "passive"))
      (node (ref "U1") (pin "BB34") (pinfunction "IO_VDD_3_BB34") (pintype "passive"))
      (node (ref "U1") (pin "BC11") (pinfunction "IO_VDD_4_BC11") (pintype "passive"))
      (node (ref "U1") (pin "BC17") (pinfunction "IO_VDD_4_BC17") (pintype "passive"))
      (node (ref "U1") (pin "BC26") (pinfunction "IO_VDD_3_BC26") (pintype "passive"))
      (node (ref "U1") (pin "BC32") (pinfunction "IO_VDD_3_BC32") (pintype "passive"))
      (node (ref "U1") (pin "BD15") (pinfunction "IO_VDD_4_BD15") (pintype "passive"))
      (node (ref "U1") (pin "C11") (pinfunction "IO_VDD_1_C11") (pintype "passive"))
      (node (ref "U1") (pin "C17") (pinfunction "IO_VDD_1_C17") (pintype "passive"))
      (node (ref "U1") (pin "C26") (pinfunction "IO_VDD_2_C26") (pintype "passive"))
      (node (ref "U1") (pin "C32") (pinfunction "IO_VDD_2_C32") (pintype "passive"))
    )
    (net (code "3") (name "/3.3V") (class "Default")
      (node (ref "C428") (pin "2") (pinfunction "2_2") (pintype "passive"))
      (node (ref "C433") (pin "2") (pinfunction "2_2") (pintype "passive"))
      (node (ref "R50") (pin "1") (pinfunction "1_1") (pintype "passive"))
      (node (ref "U10") (pin "5") (pinfunction "VCC_5") (pintype "power_in"))
      (node (ref "Y2") (pin "1") (pinfunction "OE_1") (pintype "passive"))
      (node (ref "Y2") (pin "4") (pinfunction "VDD_4") (pintype "passive"))
    )
    (net (code "4") (name "/ANAVDD_PLL_1") (class "Default")
      (node (ref "C148") (pin "1") (pinfunction "1_1") (pintype "passive"))
      (node (ref "C149") (pin "1") (pinfunction "1_1") (pintype "passive"))
      (node (ref "FB1") (pin "2") (pinfunction "2_2") (pintype "passive"))
      (node (ref "U1") (pin "A9") (pinfunction "PLL_AVDD_D1_A9") (pintype "passive"))
    )
    (net (code "5") (name "/ANAVDD_PLL_2") (class "Default")
      (node (ref "C150") (pin "1") (pinfunction "1_1") (pintype "passive"))
      (node (ref "C151") (pin "1") (pinfunction "1_1") (pintype "passive"))
      (node (ref "FB3") (pin "2") (pinfunction "2_2") (pintype "passive"))
      (node (ref "U1") (pin "A24") (pinfunction "PLL_AVDD_D2_A24") (pintype "passive"))
    )
    (net (code "6") (name "/ANAVDD_PLL_3") (class "Default")
      (node (ref "C152") (pin "1") (pinfunction "1_1") (pintype "passive"))
      (node (ref "C153") (pin "1") (pinfunction "1_1") (pintype "passive"))
      (node (ref "FB2") (pin "2") (pinfunction "2_2") (pintype "passive"))
      (node (ref "U1") (pin "BD36") (pinfunction "PLL_AVDD_D3_BD36") (pintype "passive"))
    )
    (net (code "7") (name "/ANAVDD_PLL_4") (class "Default")
      (node (ref "C154") (pin "1") (pinfunction "1_1") (pintype "passive"))
      (node (ref "C155") (pin "1") (pinfunction "1_1") (pintype "passive"))
      (node (ref "FB4") (pin "2") (pinfunction "2_2") (pintype "passive"))
      (node (ref "U1") (pin "BD21") (pinfunction "PLL_AVDD_D4_BD21") (pintype "passive"))
    )
    (net (code "8") (name "/ANAVSS_PLL_1") (class "Default")
      (node (ref "C148") (pin "2") (pinfunction "2_2") (pintype "passive"))
      (node (ref "C149") (pin "2") (pinfunction "2_2") (pintype "passive"))
      (node (ref "R61") (pin "2") (pinfunction "2_2") (pintype "passive"))
      (node (ref "U1") (pin "A10") (pinfunction "PLL_AVSS_D1_A10") (pintype "passive"))
    )
    (net (code "9") (name "/ANAVSS_PLL_2") (class "Default")
      (node (ref "C150") (pin "2") (pinfunction "2_2") (pintype "passive"))
      (node (ref "C151") (pin "2") (pinfunction "2_2") (pintype "passive"))
      (node (ref "R60") (pin "2") (pinfunction "2_2") (pintype "passive"))
      (node (ref "U1") (pin "A25") (pinfunction "PLL_AVSS_D2_A25") (pintype "passive"))
    )
    (net (code "10") (name "/ANAVSS_PLL_3") (class "Default")
      (node (ref "C152") (pin "2") (pinfunction "2_2") (pintype "passive"))
      (node (ref "C153") (pin "2") (pinfunction "2_2") (pintype "passive"))
      (node (ref "R62") (pin "2") (pinfunction "2_2") (pintype "passive"))
      (node (ref "U1") (pin "BD35") (pinfunction "PLL_AVSS_D3_BD35") (pintype "passive"))
    )
    (net (code "11") (name "/ANAVSS_PLL_4") (class "Default")
      (node (ref "C154") (pin "2") (pinfunction "2_2") (pintype "passive"))
      (node (ref "C155") (pin "2") (pinfunction "2_2") (pintype "passive"))
      (node (ref "R63") (pin "2") (pinfunction "2_2") (pintype "passive"))
      (node (ref "U1") (pin "BD20") (pinfunction "PLL_AVSS_D4_BD20") (pintype "passive"))
    )
    (net (code "12") (name "/PLL_OSC_CLK_1") (class "Default")
      (node (ref "Q49") (pin "3") (pinfunction "D_3") (pintype "passive"))
      (node (ref "R50") (pin "2") (pinfunction "2_2") (pintype "passive"))
      (node (ref "R68") (pin "1") (pinfunction "1_1") (pintype "passive"))
      (node (ref "U10") (pin "4") (pinfunction "OUTY_4") (pintype "output"))
      (node (ref "Y2") (pin "3") (pinfunction "OSC_3") (pintype "passive"))
    )
    (net (code "13") (name "/PLL_REF_CLK_1") (class "Default")
      (node (ref "Q49") (pin "1") (pinfunction "G_1") (pintype "passive"))
      (node (ref "U10") (pin "2") (pinfunction "INA_2") (pintype "input"))
    )
    (net (code "14") (name "/PLL_REF_CLK_11") (class "Default")
      (node (ref "R51") (pin "2") (pinfunction "2_2") (pintype "passive"))
      (node (ref "U1") (pin "C10") (pinfunction "CLK_IN_P_D1_C10") (pintype "passive"))
    )
    (net (code "15") (name "/PLL_REF_CLK_12") (class "Default")
      (node (ref "R52") (pin "2") (pinfunction "2_2") (pintype "passive"))
      (node (ref "U1") (pin "C25") (pinfunction "CLK_IN_P_D2_C25") (pintype "passive"))
    )
    (net (code "16") (name "/PLL_REF_CLK_13") (class "Default")
      (node (ref "R53") (pin "2") (pinfunction "2_2") (pintype "passive"))
      (node (ref "U1") (pin "BB35") (pinfunction "CLK_IN_P_D3_BB35") (pintype "passive"))
    )
    (net (code "17") (name "/PLL_REF_CLK_14") (class "Default")
      (node (ref "R54") (pin "2") (pinfunction "2_2") (pintype "passive"))
      (node (ref "U1") (pin "BB20") (pinfunction "CLK_IN_P_D4_BB20") (pintype "passive"))
    )
    (net (code "18") (name "/RESET_COLD_L") (class "Default")
      (node (ref "U1") (pin "B11") (pinfunction "HARD_RESET_D_1_B11") (pintype "passive"))
      (node (ref "U1") (pin "B26") (pinfunction "HARD_RESET_D_2_B26") (pintype "passive"))
      (node (ref "U1") (pin "BC19") (pinfunction "HARD_RESET_D_4_BC19") (pintype "passive"))
      (node (ref "U1") (pin "BC34") (pinfunction "HARD_RESET_D_3_BC34") (pintype "passive"))
    )
    (net (code "19") (name "/TXD_1") (class "Default")
      (node (ref "U1") (pin "C12") (pinfunction "RX_SERIAL_D1_C12") (pintype "passive"))
    )
    (net (code "20") (name "/TXD_2") (class "Default")
      (node (ref "U1") (pin "B12") (pinfunction "TX_SERIAL_D1_B12") (pintype "passive"))
      (node (ref "U1") (pin "C27") (pinfunction "RX_SERIAL_D2_C27") (pintype "passive"))
    )
    (net (code "21") (name "/TXD_3") (class "Default")
      (node (ref "U1") (pin "B27") (pinfunction "TX_SERIAL_D2_B27") (pintype "passive"))
      (node (ref "U1") (pin "BB33") (pinfunction "RX_SERIAL_D3_BB33") (pintype "passive"))
    )
    (net (code "22") (name "/TXD_4") (class "Default")
      (node (ref "U1") (pin "BB18") (pinfunction "RX_SERIAL_D4_BB18") (pintype "passive"))
      (node (ref "U1") (pin "BC33") (pinfunction "TX_SERIAL_D3_BC33") (pintype "passive"))
    )
    (net (code "23") (name "/TXD_5") (class "Default")
      (node (ref "U1") (pin "BC18") (pinfunction "TX_SERIAL_D4_BC18") (pintype "passive"))
    )
    (net (code "24") (name "GND") (class "Default")
      (node (ref "C164") (pin "1") (pinfunction "1_1") (pintype "passive"))
      (node (ref "C165") (pin "1") (pinfunction "1_1") (pintype "passive"))
      (node (ref "C166") (pin "1") (pinfunction "1_1") (pintype "passive"))
      (node (ref "C167") (pin "1") (pinfunction "1_1") (pintype "passive"))
      (node (ref "C428") (pin "1") (pinfunction "1_1") (pintype "passive"))
      (node (ref "C433") (pin "1") (pinfunction "1_1") (pintype "passive"))
      (node (ref "Q49") (pin "2") (pinfunction "S_2") (pintype "passive"))
      (node (ref "R19") (pin "2") (pinfunction "2_2") (pintype "passive"))
      (node (ref "R20") (pin "2") (pinfunction "2_2") (pintype "passive"))
      (node (ref "R22") (pin "2") (pinfunction "2_2") (pintype "passive"))
      (node (ref "R24") (pin "2") (pinfunction "2_2") (pintype "passive"))
      (node (ref "R25") (pin "2") (pinfunction "2_2") (pintype "passive"))
      (node (ref "R3") (pin "2") (pinfunction "2_2") (pintype "passive"))
      (node (ref "R35") (pin "2") (pinfunction "2_2") (pintype "passive"))
      (node (ref "R36") (pin "2") (pinfunction "2_2") (pintype "passive"))
      (node (ref "R37") (pin "2") (pinfunction "2_2") (pintype "passive"))
      (node (ref "R38") (pin "2") (pinfunction "2_2") (pintype "passive"))
      (node (ref "R39") (pin "2") (pinfunction "2_2") (pintype "passive"))
      (node (ref "R40") (pin "2") (pinfunction "2_2") (pintype "passive"))
      (node (ref "R60") (pin "1") (pinfunction "1_1") (pintype "passive"))
      (node (ref "R61") (pin "1") (pinfunction "1_1") (pintype "passive"))
      (node (ref "R62") (pin "1") (pinfunction "1_1") (pintype "passive"))
      (node (ref "R63") (pin "1") (pinfunction "1_1") (pintype "passive"))
      (node (ref "R69") (pin "2") (pinfunction "2_2") (pintype "passive"))
      (node (ref "U1") (pin "A12") (pinfunction "IO_VSS_1_A12") (pintype "passive"))
      (node (ref "U1") (pin "A18") (pinfunction "IO_VSS_1_A18") (pintype "passive"))
      (node (ref "U1") (pin "A27") (pinfunction "IO_VSS_2_A27") (pintype "passive"))
      (node (ref "U1") (pin "A33") (pinfunction "IO_VSS_2_A33") (pintype "passive"))
      (node (ref "U1") (pin "B10") (pinfunction "IO_VSS_1_B10") (pintype "passive"))
      (node (ref "U1") (pin "B16") (pinfunction "IO_VSS_1_B16") (pintype "passive"))
      (node (ref "U1") (pin "B24") (pinfunction "IO_VSS_2_B24") (pintype "passive"))
      (node (ref "U1") (pin "B25") (pinfunction "IO_VSS_2_B25") (pintype "passive"))
      (node (ref "U1") (pin "B31") (pinfunction "IO_VSS_2_B31") (pintype "passive"))
      (node (ref "U1") (pin "B9") (pinfunction "IO_VSS_1_B9") (pintype "passive"))
      (node (ref "U1") (pin "BB10") (pinfunction "IO_VSS_4_BB10") (pintype "passive"))
      (node (ref "U1") (pin "BB16") (pinfunction "IO_VSS_4_BB16") (pintype "passive"))
      (node (ref "U1") (pin "BB25") (pinfunction "IO_VSS_3_BB25") (pintype "passive"))
      (node (ref "U1") (pin "BB31") (pinfunction "IO_VSS_3_BB31") (pintype "passive"))
      (node (ref "U1") (pin "BC14") (pinfunction "IO_VSS_4_BC14") (pintype "passive"))
      (node (ref "U1") (pin "BC20") (pinfunction "IO_VSS_4_BC20") (pintype "passive"))
      (node (ref "U1") (pin "BC21") (pinfunction "IO_VSS_4_BC21") (pintype "passive"))
      (node (ref "U1") (pin "BC29") (pinfunction "IO_VSS_3_BC29") (pintype "passive"))
      (node (ref "U1") (pin "BC35") (pinfunction "IO_VSS_3_BC35") (pintype "passive"))
      (node (ref "U1") (pin "BC36") (pinfunction "IO_VSS_3_BC36") (pintype "passive"))
      (node (ref "U1") (pin "BD18") (pinfunction "IO_VSS_4_BD18") (pintype "passive"))
      (node (ref "U1") (pin "BD27") (pinfunction "IO_VSS_3_BD27") (pintype "passive"))
      (node (ref "U1") (pin "BD33") (pinfunction "IO_VSS_3_BD33") (pintype "passive"))
      (node (ref "U1") (pin "C14") (pinfunction "IO_VSS_1_C14") (pintype "passive"))
      (node (ref "U1") (pin "C20") (pinfunction "IO_VSS_1_C20") (pintype "passive"))
      (node (ref "U1") (pin "C29") (pinfunction "IO_VSS_2_C29") (pintype "passive"))
      (node (ref "U1") (pin "C35") (pinfunction "IO_VSS_2_C35") (pintype "passive"))
      (node (ref "U10") (pin "1") (pinfunction "~{OE}_1") (pintype "input"))
      (node (ref "U10") (pin "3") (pinfunction "GND_3") (pintype "power_in"))
      (node (ref "Y2") (pin "2") (pinfunction "GND_2") (pintype "passive"))
    )
    (net (code "25") (name "Net-(R51-Pad1)") (class "Default")
      (node (ref "R51") (pin "1") (pinfunction "1_1") (pintype "passive"))
      (node (ref "R52") (pin "1") (pinfunction "1_1") (pintype "passive"))
      (node (ref "R53") (pin "1") (pinfunction "1_1") (pintype "passive"))
      (node (ref "R54") (pin "1") (pinfunction "1_1") (pintype "passive"))
      (node (ref "R68") (pin "2") (pinfunction "2_2") (pintype "passive"))
      (node (ref "R69") (pin "1") (pinfunction "1_1") (pintype "passive"))
    )
    (net (code "26") (name "Net-(TP133-Pad1)") (class "Default")
      (node (ref "TP133") (pin "1") (pinfunction "1_1") (pintype "passive"))
      (node (ref "U1") (pin "BB20") (pinfunction "IO_VDD_4_BB20") (pintype "passive"))
    )
    (net (code "27") (name "Net-(TP134-Pad1)") (class "Default")
      (node (ref "TP134") (pin "1") (pinfunction "1_1") (pintype "passive"))
      (node (ref "U1") (pin "BD31") (pinfunction "IO_VDD_3_BD31") (pintype "passive"))
    )
    (net (code "28") (name "Net-(TP135-Pad1)") (class "Default")
      (node (ref "TP135") (pin "1") (pinfunction "1_1") (pintype "passive"))
      (node (ref "U1") (pin "BD12") (pinfunction "IO_VSS_4_BD12") (pintype "passive"))
    )
    (net (code "29") (name "Net-(U1B-GPI[0]_D1)") (class "Default")
      (node (ref "TP50") (pin "1") (pinfunction "1_1") (pintype "passive"))
      (node (ref "U1") (pin "A13") (pinfunction "GPI[0]_D1_A13") (pintype "passive"))
    )
    (net (code "30") (name "Net-(U1B-GPI[1]_D1)") (class "Default")
      (node (ref "TP78") (pin "1") (pinfunction "1_1") (pintype "passive"))
      (node (ref "U1") (pin "C13") (pinfunction "GPI[1]_D1_C13") (pintype "passive"))
    )
    (net (code "31") (name "Net-(U1B-GPI[2]_D1)") (class "Default")
      (node (ref "TP26") (pin "1") (pinfunction "1_1") (pintype "passive"))
      (node (ref "U1") (pin "A14") (pinfunction "GPI[2]_D1_A14") (pintype "passive"))
    )
    (net (code "32") (name "Net-(U1B-GPI[3]_D1)") (class "Default")
      (node (ref "TP70") (pin "1") (pinfunction "1_1") (pintype "passive"))
      (node (ref "U1") (pin "B14") (pinfunction "GPI[3]_D1_B14") (pintype "passive"))
    )
    (net (code "33") (name "Net-(U1B-GPI[4]_D1)") (class "Default")
      (node (ref "TP22") (pin "1") (pinfunction "1_1") (pintype "passive"))
      (node (ref "U1") (pin "B15") (pinfunction "GPI[4]_D1_B15") (pintype "passive"))
    )
    (net (code "34") (name "Net-(U1B-GPI[5]_D1)") (class "Default")
      (node (ref "R25") (pin "1") (pinfunction "1_1") (pintype "passive"))
      (node (ref "U1") (pin "C15") (pinfunction "GPI[5]_D1_C15") (pintype "passive"))
    )
    (net (code "35") (name "Net-(U1B-GPI[6]_D1)") (class "Default")
      (node (ref "R19") (pin "1") (pinfunction "1_1") (pintype "passive"))
      (node (ref "U1") (pin "A16") (pinfunction "GPI[6]_D1_A16") (pintype "passive"))
    )
    (net (code "36") (name "Net-(U1B-GPI[7]_D1)") (class "Default")
      (node (ref "R3") (pin "1") (pinfunction "1_1") (pintype "passive"))
      (node (ref "U1") (pin "C16") (pinfunction "GPI[7]_D1_C16") (pintype "passive"))
    )
    (net (code "37") (name "Net-(U1B-GPO[0]_D1)") (class "Default")
      (node (ref "TP95") (pin "1") (pinfunction "1_1") (pintype "passive"))
      (node (ref "U1") (pin "A17") (pinfunction "GPO[0]_D1_A17") (pintype "passive"))
    )
    (net (code "38") (name "Net-(U1B-GPO[1]_D1)") (class "Default")
      (node (ref "TP96") (pin "1") (pinfunction "1_1") (pintype "passive"))
      (node (ref "U1") (pin "B17") (pinfunction "GPO[1]_D1_B17") (pintype "passive"))
    )
    (net (code "39") (name "Net-(U1B-GPO[2]_D1)") (class "Default")
      (node (ref "TP97") (pin "1") (pinfunction "1_1") (pintype "passive"))
      (node (ref "U1") (pin "B18") (pinfunction "GPO[2]_D1_B18") (pintype "passive"))
    )
    (net (code "40") (name "Net-(U1B-GPO[3]_D1)") (class "Default")
      (node (ref "TP98") (pin "1") (pinfunction "1_1") (pintype "passive"))
      (node (ref "U1") (pin "C18") (pinfunction "GPO[3]_D1_C18") (pintype "passive"))
    )
    (net (code "41") (name "Net-(U1B-GPO[4]_D1)") (class "Default")
      (node (ref "TP99") (pin "1") (pinfunction "1_1") (pintype "passive"))
      (node (ref "U1") (pin "A19") (pinfunction "GPO[4]_D1_A19") (pintype "passive"))
    )
    (net (code "42") (name "Net-(U1B-GPO[5]_D1)") (class "Default")
      (node (ref "TP46") (pin "1") (pinfunction "1_1") (pintype "passive"))
      (node (ref "U1") (pin "A20") (pinfunction "GPO[5]_D1_A20") (pintype "passive"))
    )
    (net (code "43") (name "Net-(U1B-GPO[6]_D1)") (class "Default")
      (node (ref "TP42") (pin "1") (pinfunction "1_1") (pintype "passive"))
      (node (ref "U1") (pin "B20") (pinfunction "GPO[6]_D1_B20") (pintype "passive"))
    )
    (net (code "44") (name "Net-(U1B-GPO[7]_D1)") (class "Default")
      (node (ref "TP38") (pin "1") (pinfunction "1_1") (pintype "passive"))
      (node (ref "U1") (pin "A21") (pinfunction "GPO[7]_D1_A21") (pintype "passive"))
    )
    (net (code "45") (name "Net-(U1B-MODE_D1)") (class "Default")
      (node (ref "R27") (pin "2") (pinfunction "2_2") (pintype "passive"))
      (node (ref "U1") (pin "A11") (pinfunction "MODE_D1_A11") (pintype "passive"))
    )
    (net (code "46") (name "Net-(U1B-VTRIM_D1)") (class "Default")
      (node (ref "TP115") (pin "1") (pinfunction "1_1") (pintype "passive"))
      (node (ref "U1") (pin "C19") (pinfunction "VTRIM_D1_C19") (pintype "passive"))
    )
    (net (code "47") (name "Net-(U1C-GPI[0]_D2)") (class "Default")
      (node (ref "TP104") (pin "1") (pinfunction "1_1") (pintype "passive"))
      (node (ref "U1") (pin "A28") (pinfunction "GPI[0]_D2_A28") (pintype "passive"))
    )
    (net (code "48") (name "Net-(U1C-GPI[1]_D2)") (class "Default")
      (node (ref "TP107") (pin "1") (pinfunction "1_1") (pintype "passive"))
      (node (ref "U1") (pin "C28") (pinfunction "GPI[1]_D2_C28") (pintype "passive"))
    )
    (net (code "49") (name "Net-(U1C-GPI[2]_D2)") (class "Default")
      (node (ref "TP110") (pin "1") (pinfunction "1_1") (pintype "passive"))
      (node (ref "U1") (pin "A29") (pinfunction "GPI[2]_D2_A29") (pintype "passive"))
    )
    (net (code "50") (name "Net-(U1C-GPI[3]_D2)") (class "Default")
      (node (ref "TP79") (pin "1") (pinfunction "1_1") (pintype "passive"))
      (node (ref "U1") (pin "B29") (pinfunction "GPI[3]_D2_B29") (pintype "passive"))
    )
    (net (code "51") (name "Net-(U1C-GPI[4]_D2)") (class "Default")
      (node (ref "TP23") (pin "1") (pinfunction "1_1") (pintype "passive"))
      (node (ref "U1") (pin "B30") (pinfunction "GPI[4]_D2_B30") (pintype "passive"))
    )
    (net (code "52") (name "Net-(U1C-GPI[5]_D2)") (class "Default")
      (node (ref "R39") (pin "1") (pinfunction "1_1") (pintype "passive"))
      (node (ref "U1") (pin "C30") (pinfunction "GPI[5]_D2_C30") (pintype "passive"))
    )
    (net (code "53") (name "Net-(U1C-GPI[6]_D2)") (class "Default")
      (node (ref "R20") (pin "1") (pinfunction "1_1") (pintype "passive"))
      (node (ref "U1") (pin "A31") (pinfunction "GPI[6]_D2_A31") (pintype "passive"))
    )
    (net (code "54") (name "Net-(U1C-GPI[7]_D2)") (class "Default")
      (node (ref "R36") (pin "1") (pinfunction "1_1") (pintype "passive"))
      (node (ref "U1") (pin "C31") (pinfunction "GPI[7]_D2_C31") (pintype "passive"))
    )
    (net (code "55") (name "Net-(U1C-GPO[0]_D2)") (class "Default")
      (node (ref "TP51") (pin "1") (pinfunction "1_1") (pintype "passive"))
      (node (ref "U1") (pin "A32") (pinfunction "GPO[0]_D2_A32") (pintype "passive"))
    )
    (net (code "56") (name "Net-(U1C-GPO[1]_D2)") (class "Default")
      (node (ref "TP47") (pin "1") (pinfunction "1_1") (pintype "passive"))
      (node (ref "U1") (pin "B32") (pinfunction "GPO[1]_D2_B32") (pintype "passive"))
    )
    (net (code "57") (name "Net-(U1C-GPO[2]_D2)") (class "Default")
      (node (ref "TP43") (pin "1") (pinfunction "1_1") (pintype "passive"))
      (node (ref "U1") (pin "B33") (pinfunction "GPO[2]_D2_B33") (pintype "passive"))
    )
    (net (code "58") (name "Net-(U1C-GPO[3]_D2)") (class "Default")
      (node (ref "TP39") (pin "1") (pinfunction "1_1") (pintype "passive"))
      (node (ref "U1") (pin "C33") (pinfunction "GPO[3]_D2_C33") (pintype "passive"))
    )
    (net (code "59") (name "Net-(U1C-GPO[4]_D2)") (class "Default")
      (node (ref "TP27") (pin "1") (pinfunction "1_1") (pintype "passive"))
      (node (ref "U1") (pin "A34") (pinfunction "GPO[4]_D2_A34") (pintype "passive"))
    )
    (net (code "60") (name "Net-(U1C-GPO[5]_D2)") (class "Default")
      (node (ref "TP71") (pin "1") (pinfunction "1_1") (pintype "passive"))
      (node (ref "U1") (pin "A35") (pinfunction "GPO[5]_D2_A35") (pintype "passive"))
    )
    (net (code "61") (name "Net-(U1C-GPO[6]_D2)") (class "Default")
      (node (ref "TP100") (pin "1") (pinfunction "1_1") (pintype "passive"))
      (node (ref "U1") (pin "B35") (pinfunction "GPO[6]_D2_B35") (pintype "passive"))
    )
    (net (code "62") (name "Net-(U1C-GPO[7]_D2)") (class "Default")
      (node (ref "TP101") (pin "1") (pinfunction "1_1") (pintype "passive"))
      (node (ref "U1") (pin "A36") (pinfunction "GPO[7]_D2_A36") (pintype "passive"))
    )
    (net (code "63") (name "Net-(U1C-MODE_D2)") (class "Default")
      (node (ref "R28") (pin "2") (pinfunction "2_2") (pintype "passive"))
      (node (ref "U1") (pin "A26") (pinfunction "MODE_D2_A26") (pintype "passive"))
    )
    (net (code "64") (name "Net-(U1C-VTRIM_D2)") (class "Default")
      (node (ref "TP116") (pin "1") (pinfunction "1_1") (pintype "passive"))
      (node (ref "U1") (pin "C34") (pinfunction "VTRIM_D2_C34") (pintype "passive"))
    )
    (net (code "65") (name "Net-(U1D-GPI[0]_D3)") (class "Default")
      (node (ref "TP105") (pin "1") (pinfunction "1_1") (pintype "passive"))
      (node (ref "U1") (pin "BD32") (pinfunction "GPI[0]_D3_BD32") (pintype "passive"))
    )
    (net (code "66") (name "Net-(U1D-GPI[1]_D3)") (class "Default")
      (node (ref "TP108") (pin "1") (pinfunction "1_1") (pintype "passive"))
      (node (ref "U1") (pin "BB32") (pinfunction "GPI[1]_D3_BB32") (pintype "passive"))
    )
    (net (code "67") (name "Net-(U1D-GPI[2]_D3)") (class "Default")
      (node (ref "TP111") (pin "1") (pinfunction "1_1") (pintype "passive"))
      (node (ref "U1") (pin "BD31") (pinfunction "GPI[2]_D3_BD31") (pintype "passive"))
    )
    (net (code "68") (name "Net-(U1D-GPI[3]_D3)") (class "Default")
      (node (ref "TP113") (pin "1") (pinfunction "1_1") (pintype "passive"))
      (node (ref "U1") (pin "BC31") (pinfunction "GPI[3]_D3_BC31") (pintype "passive"))
    )
    (net (code "69") (name "Net-(U1D-GPI[4]_D3)") (class "Default")
      (node (ref "TP24") (pin "1") (pinfunction "1_1") (pintype "passive"))
      (node (ref "U1") (pin "BC30") (pinfunction "GPI[4]_D3_BC30") (pintype "passive"))
    )
    (net (code "70") (name "Net-(U1D-GPI[5]_D3)") (class "Default")
      (node (ref "R35") (pin "1") (pinfunction "1_1") (pintype "passive"))
      (node (ref "U1") (pin "BB30") (pinfunction "GPI[5]_D3_BB30") (pintype "passive"))
    )
    (net (code "71") (name "Net-(U1D-GPI[6]_D3)") (class "Default")
      (node (ref "R24") (pin "1") (pinfunction "1_1") (pintype "passive"))
      (node (ref "U1") (pin "BD29") (pinfunction "GPI[6]_D3_BD29") (pintype "passive"))
    )
    (net (code "72") (name "Net-(U1D-GPI[7]_D3)") (class "Default")
      (node (ref "R22") (pin "1") (pinfunction "1_1") (pintype "passive"))
      (node (ref "U1") (pin "BB29") (pinfunction "GPI[7]_D3_BB29") (pintype "passive"))
    )
    (net (code "73") (name "Net-(U1D-GPO[0]_D3)") (class "Default")
      (node (ref "TP52") (pin "1") (pinfunction "1_1") (pintype "passive"))
      (node (ref "U1") (pin "BD28") (pinfunction "GPO[0]_D3_BD28") (pintype "passive"))
    )
    (net (code "74") (name "Net-(U1D-GPO[1]_D3)") (class "Default")
      (node (ref "TP48") (pin "1") (pinfunction "1_1") (pintype "passive"))
      (node (ref "U1") (pin "BC28") (pinfunction "GPO[1]_D3_BC28") (pintype "passive"))
    )
    (net (code "75") (name "Net-(U1D-GPO[2]_D3)") (class "Default")
      (node (ref "TP44") (pin "1") (pinfunction "1_1") (pintype "passive"))
      (node (ref "U1") (pin "BC27") (pinfunction "GPO[2]_D3_BC27") (pintype "passive"))
    )
    (net (code "76") (name "Net-(U1D-GPO[3]_D3)") (class "Default")
      (node (ref "TP40") (pin "1") (pinfunction "1_1") (pintype "passive"))
      (node (ref "U1") (pin "BB27") (pinfunction "GPO[3]_D3_BB27") (pintype "passive"))
    )
    (net (code "77") (name "Net-(U1D-GPO[4]_D3)") (class "Default")
      (node (ref "TP72") (pin "1") (pinfunction "1_1") (pintype "passive"))
      (node (ref "U1") (pin "BD26") (pinfunction "GPO[4]_D3_BD26") (pintype "passive"))
    )
    (net (code "78") (name "Net-(U1D-GPO[5]_D3)") (class "Default")
      (node (ref "TP80") (pin "1") (pinfunction "1_1") (pintype "passive"))
      (node (ref "U1") (pin "BD25") (pinfunction "GPO[5]_D3_BD25") (pintype "passive"))
    )
    (net (code "79") (name "Net-(U1D-GPO[6]_D3)") (class "Default")
      (node (ref "TP28") (pin "1") (pinfunction "1_1") (pintype "passive"))
      (node (ref "U1") (pin "BC25") (pinfunction "GPO[6]_D3_BC25") (pintype "passive"))
    )
    (net (code "80") (name "Net-(U1D-GPO[7]_D3)") (class "Default")
      (node (ref "TP102") (pin "1") (pinfunction "1_1") (pintype "passive"))
      (node (ref "U1") (pin "BD24") (pinfunction "GPO[7]_D3_BD24") (pintype "passive"))
    )
    (net (code "81") (name "Net-(U1D-MODE_D3)") (class "Default")
      (node (ref "R29") (pin "2") (pinfunction "2_2") (pintype "passive"))
      (node (ref "U1") (pin "BD34") (pinfunction "MODE_D3_BD34") (pintype "passive"))
    )
    (net (code "82") (name "Net-(U1D-VTRIM_D3)") (class "Default")
      (node (ref "TP117") (pin "1") (pinfunction "1_1") (pintype "passive"))
      (node (ref "U1") (pin "BB26") (pinfunction "VTRIM_D3_BB26") (pintype "passive"))
    )
    (net (code "83") (name "Net-(U1E-GPI[0]_D4)") (class "Default")
      (node (ref "TP106") (pin "1") (pinfunction "1_1") (pintype "passive"))
      (node (ref "U1") (pin "BD17") (pinfunction "GPI[0]_D4_BD17") (pintype "passive"))
    )
    (net (code "84") (name "Net-(U1E-GPI[1]_D4)") (class "Default")
      (node (ref "TP109") (pin "1") (pinfunction "1_1") (pintype "passive"))
      (node (ref "U1") (pin "BB17") (pinfunction "GPI[1]_D4_BB17") (pintype "passive"))
    )
    (net (code "85") (name "Net-(U1E-GPI[2]_D4)") (class "Default")
      (node (ref "TP112") (pin "1") (pinfunction "1_1") (pintype "passive"))
      (node (ref "U1") (pin "BD16") (pinfunction "GPI[2]_D4_BD16") (pintype "passive"))
    )
    (net (code "86") (name "Net-(U1E-GPI[3]_D4)") (class "Default")
      (node (ref "TP114") (pin "1") (pinfunction "1_1") (pintype "passive"))
      (node (ref "U1") (pin "BC16") (pinfunction "GPI[3]_D4_BC16") (pintype "passive"))
    )
    (net (code "87") (name "Net-(U1E-GPI[4]_D4)") (class "Default")
      (node (ref "TP25") (pin "1") (pinfunction "1_1") (pintype "passive"))
      (node (ref "U1") (pin "BC15") (pinfunction "GPI[4]_D4_BC15") (pintype "passive"))
    )
    (net (code "88") (name "Net-(U1E-GPI[5]_D4)") (class "Default")
      (node (ref "R40") (pin "1") (pinfunction "1_1") (pintype "passive"))
      (node (ref "U1") (pin "BB15") (pinfunction "GPI[5]_D4_BB15") (pintype "passive"))
    )
    (net (code "89") (name "Net-(U1E-GPI[6]_D4)") (class "Default")
      (node (ref "R38") (pin "1") (pinfunction "1_1") (pintype "passive"))
      (node (ref "U1") (pin "BD14") (pinfunction "GPI[6]_D4_BD14") (pintype "passive"))
    )
    (net (code "90") (name "Net-(U1E-GPI[7]_D4)") (class "Default")
      (node (ref "R37") (pin "1") (pinfunction "1_1") (pintype "passive"))
      (node (ref "U1") (pin "BB14") (pinfunction "GPI[7]_D4_BB14") (pintype "passive"))
    )
    (net (code "91") (name "Net-(U1E-GPO[0]_D4)") (class "Default")
      (node (ref "TP73") (pin "1") (pinfunction "1_1") (pintype "passive"))
      (node (ref "U1") (pin "BD13") (pinfunction "GPO[0]_D4_BD13") (pintype "passive"))
    )
    (net (code "92") (name "Net-(U1E-GPO[1]_D4)") (class "Default")
      (node (ref "TP53") (pin "1") (pinfunction "1_1") (pintype "passive"))
      (node (ref "U1") (pin "BC13") (pinfunction "GPO[1]_D4_BC13") (pintype "passive"))
    )
    (net (code "93") (name "Net-(U1E-GPO[2]_D4)") (class "Default")
      (node (ref "TP49") (pin "1") (pinfunction "1_1") (pintype "passive"))
      (node (ref "U1") (pin "BC12") (pinfunction "GPO[2]_D4_BC12") (pintype "passive"))
    )
    (net (code "94") (name "Net-(U1E-GPO[3]_D4)") (class "Default")
      (node (ref "TP45") (pin "1") (pinfunction "1_1") (pintype "passive"))
      (node (ref "U1") (pin "BD12") (pinfunction "GPO[3]_D4_BD12") (pintype "passive"))
    )
    (net (code "95") (name "Net-(U1E-GPO[4]_D4)") (class "Default")
      (node (ref "TP41") (pin "1") (pinfunction "1_1") (pintype "passive"))
      (node (ref "U1") (pin "BD11") (pinfunction "GPO[4]_D4_BD11") (pintype "passive"))
    )
    (net (code "96") (name "Net-(U1E-GPO[5]_D4)") (class "Default")
      (node (ref "TP81") (pin "1") (pinfunction "1_1") (pintype "passive"))
      (node (ref "U1") (pin "BD10") (pinfunction "GPO[5]_D4_BD10") (pintype "passive"))
    )
    (net (code "97") (name "Net-(U1E-GPO[6]_D4)") (class "Default")
      (node (ref "TP29") (pin "1") (pinfunction "1_1") (pintype "passive"))
      (node (ref "U1") (pin "BC10") (pinfunction "GPO[6]_D4_BC10") (pintype "passive"))
    )
    (net (code "98") (name "Net-(U1E-GPO[7]_D4)") (class "Default")
      (node (ref "TP103") (pin "1") (pinfunction "1_1") (pintype "passive"))
      (node (ref "U1") (pin "BD9") (pinfunction "GPO[7]_D4_BD9") (pintype "passive"))
    )
    (net (code "99") (name "Net-(U1E-MODE_D4)") (class "Default")
      (node (ref "R30") (pin "2") (pinfunction "2_2") (pintype "passive"))
      (node (ref "U1") (pin "BD19") (pinfunction "MODE_D4_BD19") (pintype "passive"))
    )
    (net (code "100") (name "Net-(U1E-VTRIM_D4)") (class "Default")
      (node (ref "TP118") (pin "1") (pinfunction "1_1") (pintype "passive"))
      (node (ref "U1") (pin "BB11") (pinfunction "VTRIM_D4_BB11") (pintype "passive"))
    )
  )
)
